# MCUAntenna.net
KiCad netlist of a schematic drawn in Altium Designer
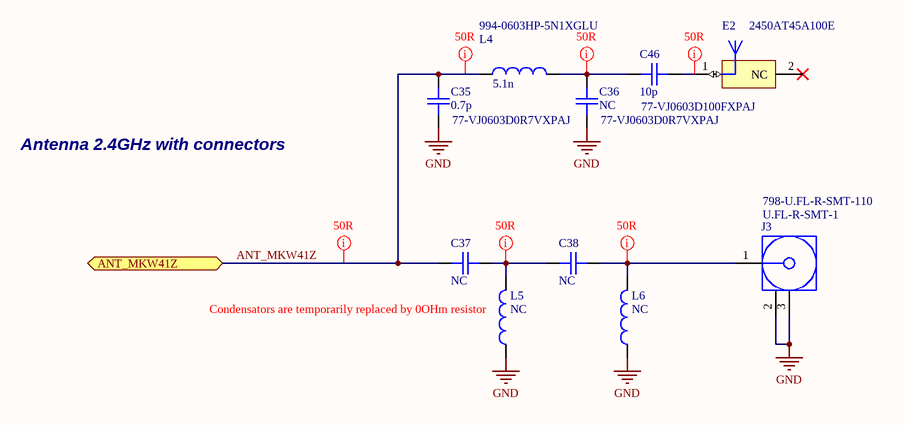
[diagram p0: MCUAntenna.SchDoc]

(export (version "E")
  (design (tool "Eeschema 10.0.6"))
  (components
    (comp (ref "C35")
      (value "0.7p")
      (footprint "CAPC1608X08")
      (description "MLCC Capacitor 1608")
      (fields (field (name "SUPPLIER PART NUMBER 1") "77-VJ0603D0R7VXPAJ"))
      (libsource (lib "HEPIA Vault") (part "CMP-001-0010-A.3"))
    )
    (comp (ref "C36")
      (value "NC")
      (footprint "CAPC1608X08")
      (description "MLCC Capacitor 1608")
      (fields (field (name "SUPPLIER PART NUMBER 1") "77-VJ0603D0R7VXPAJ"))
      (libsource (lib "HEPIA Vault") (part "CMP-001-0010-A.3"))
    )
    (comp (ref "C37")
      (value "NC")
      (footprint "CAPC1608X08")
      (description "MLCC Capacitor 1608")
      (libsource (lib "HEPIA Vault") (part "CMP-001-0010-A.3"))
    )
    (comp (ref "C38")
      (value "NC")
      (footprint "CAPC1608X08")
      (description "MLCC Capacitor 1608")
      (libsource (lib "HEPIA Vault") (part "CMP-001-0010-A.3"))
    )
    (comp (ref "C46")
      (value "10p")
      (footprint "CAPC1608X08")
      (description "MLCC Capacitor 1608")
      (fields (field (name "SUPPLIER PART NUMBER 1") "77-VJ0603D100FXPAJ"))
      (libsource (lib "HEPIA Vault") (part "CMP-001-0010-A.3"))
    )
    (comp (ref "E2")
      (value "2450AT45A100E")
      (footprint "Antenne 2.4ghz Ceramique")
      (description "Antennas 2.45GHz ANTENNA HIGH GAIN (VERT)")
      (libsource (lib "HEPIA Vault") (part "2450AT"))
    )
    (comp (ref "J3")
      (value "U.FL-R-SMT-1")
      (footprint "U.FL-R-SMT-1")
      (description "Hirose U.FL SMT connector")
      (fields (field (name "SUPPLIER PART NUMBER 1") "798-U.FL-R-SMT-110"))
      (libsource (lib "HEPIA Vault") (part "CMP-001-0013-A.3"))
    )
    (comp (ref "L4")
      (value "5.1n")
      (footprint "INDC1608X08")
      (description "Ferrite Beads 1608")
      (fields (field (name "SUPPLIER PART NUMBER 1") "994-0603HP-5N1XGLU"))
      (libsource (lib "HEPIA Vault") (part "CMP-001-0101-A.4"))
    )
    (comp (ref "L5")
      (value "NC")
      (footprint "INDC1608X08")
      (description "Ferrite Beads 1608")
      (libsource (lib "HEPIA Vault") (part "CMP-001-0101-A.4"))
    )
    (comp (ref "L6")
      (value "NC")
      (footprint "INDC1608X08")
      (description "Ferrite Beads 1608")
      (libsource (lib "HEPIA Vault") (part "CMP-001-0101-A.4"))
    )
  )
  (nets
    (net (code "1") (name "/ANT_MKW41Z") (class "Default")
      (node (ref "C35") (pin "2") (pinfunction "2_2") (pintype "passive"))
      (node (ref "C37") (pin "1") (pinfunction "1_1") (pintype "passive"))
      (node (ref "L4") (pin "1") (pinfunction "1_1") (pintype "passive"))
    )
    (net (code "2") (name "GND") (class "Default")
      (node (ref "C35") (pin "1") (pinfunction "1_1") (pintype "passive"))
      (node (ref "C36") (pin "1") (pinfunction "1_1") (pintype "passive"))
      (node (ref "J3") (pin "2") (pinfunction "GND_2") (pintype "power_in"))
      (node (ref "J3") (pin "3") (pinfunction "GND_3") (pintype "power_in"))
      (node (ref "L5") (pin "1") (pinfunction "1_1") (pintype "passive"))
      (node (ref "L6") (pin "1") (pinfunction "1_1") (pintype "passive"))
    )
    (net (code "3") (name "Net-(C36-Pad2)") (class "Default")
      (node (ref "C36") (pin "2") (pinfunction "2_2") (pintype "passive"))
      (node (ref "C46") (pin "1") (pinfunction "1_1") (pintype "passive"))
      (node (ref "L4") (pin "2") (pinfunction "2_2") (pintype "passive"))
    )
    (net (code "4") (name "Net-(C37-Pad2)") (class "Default")
      (node (ref "C37") (pin "2") (pinfunction "2_2") (pintype "passive"))
      (node (ref "C38") (pin "1") (pinfunction "1_1") (pintype "passive"))
      (node (ref "L5") (pin "2") (pinfunction "2_2") (pintype "passive"))
    )
    (net (code "5") (name "Net-(E2-FEED)") (class "Default")
      (node (ref "C46") (pin "2") (pinfunction "2_2") (pintype "passive"))
      (node (ref "E2") (pin "1") (pinfunction "FEED_1") (pintype "bidirectional"))
    )
    (net (code "6") (name "Net-(J3-Signal)") (class "Default")
      (node (ref "C38") (pin "2") (pinfunction "2_2") (pintype "passive"))
      (node (ref "J3") (pin "1") (pinfunction "Signal_1") (pintype "passive"))
      (node (ref "L6") (pin "2") (pinfunction "2_2") (pintype "passive"))
    )
    (net (code "7") (name "unconnected-(E2-NC-Pad2)") (class "Default")
      (node (ref "E2") (pin "2") (pinfunction "NC_2") (pintype "passive+no_connect"))
    )
  )
)
